# Borne_de_satisfaction_V0.net
KiCad netlist of a schematic drawn in EAGLE
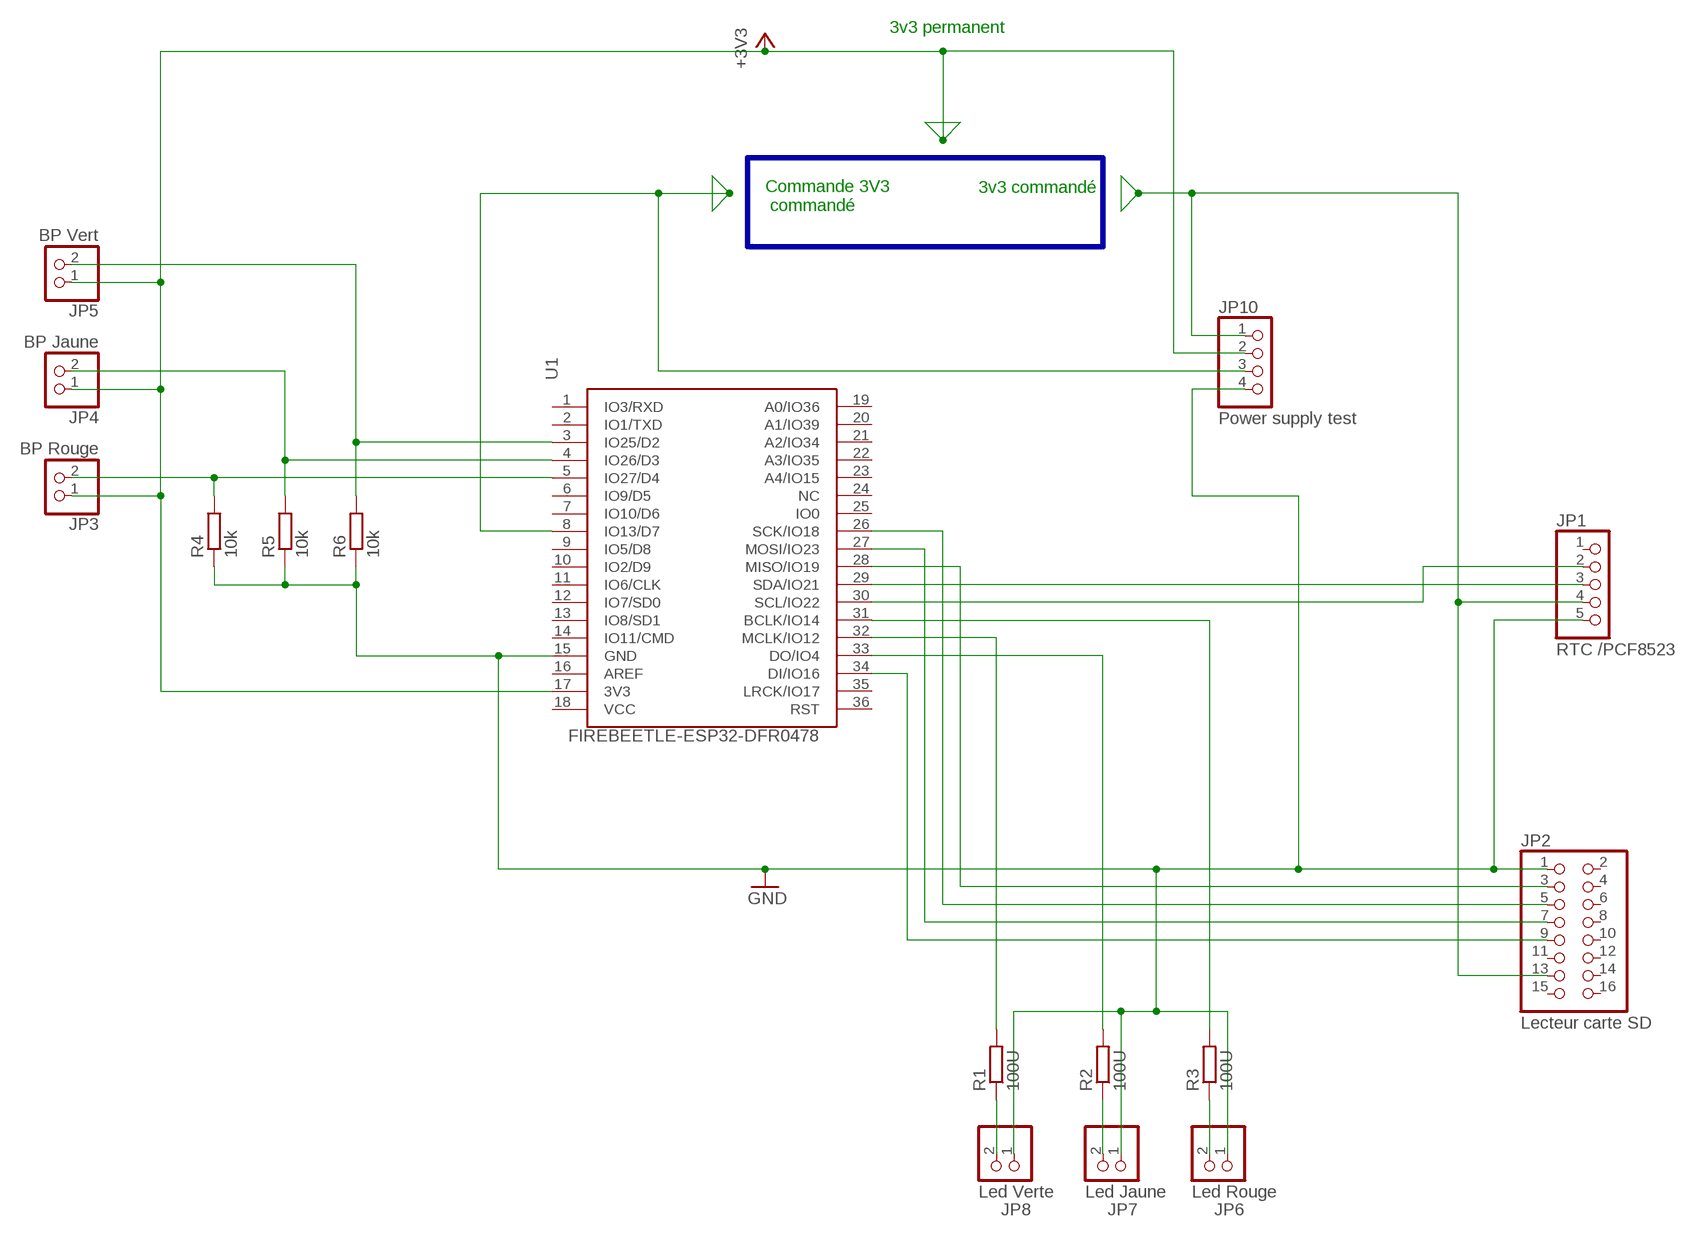
[diagram p0: schematic, sheet 1]

(export (version "E")
  (design (tool "Eeschema 10.0.6"))
  (components
    (comp (ref "JP1")
      (value "RTC /PCF8523")
      (footprint "eagle-import:1X05")
      (libsource (lib "eagle-import") (part "PINHD-1X5"))
    )
    (comp (ref "JP2")
      (value "Lecteur carte SD")
      (footprint "eagle-import:2X08")
      (libsource (lib "eagle-import") (part "PINHD-2X8"))
    )
    (comp (ref "JP3")
      (value "BP Rouge")
      (footprint "eagle-import:1X02")
      (libsource (lib "eagle-import") (part "PINHD-1X2"))
    )
    (comp (ref "JP4")
      (value "BP Jaune")
      (footprint "eagle-import:1X02")
      (libsource (lib "eagle-import") (part "PINHD-1X2"))
    )
    (comp (ref "JP5")
      (value "BP Vert")
      (footprint "eagle-import:1X02")
      (libsource (lib "eagle-import") (part "PINHD-1X2"))
    )
    (comp (ref "JP6")
      (value "Led Rouge")
      (footprint "eagle-import:1X02")
      (libsource (lib "eagle-import") (part "PINHD-1X2"))
    )
    (comp (ref "JP7")
      (value "Led Jaune")
      (footprint "eagle-import:1X02")
      (libsource (lib "eagle-import") (part "PINHD-1X2"))
    )
    (comp (ref "JP8")
      (value "Led Verte")
      (footprint "eagle-import:1X02")
      (libsource (lib "eagle-import") (part "PINHD-1X2"))
    )
    (comp (ref "JP10")
      (value "Power supply test")
      (footprint "eagle-import:1X04")
      (libsource (lib "eagle-import") (part "PINHD-1X4"))
    )
    (comp (ref "R1")
      (value "100U")
      (footprint "eagle-import:0207_10")
      (libsource (lib "eagle-import") (part "R-EU_0207/10"))
    )
    (comp (ref "R2")
      (value "100U")
      (footprint "eagle-import:0207_10")
      (libsource (lib "eagle-import") (part "R-EU_0207/10"))
    )
    (comp (ref "R3")
      (value "100U")
      (footprint "eagle-import:0207_10")
      (libsource (lib "eagle-import") (part "R-EU_0207/10"))
    )
    (comp (ref "R4")
      (value "10k")
      (footprint "eagle-import:0207_10")
      (libsource (lib "eagle-import") (part "R-EU_0207/10"))
    )
    (comp (ref "R5")
      (value "10k")
      (footprint "eagle-import:0207_10")
      (libsource (lib "eagle-import") (part "R-EU_0207/10"))
    )
    (comp (ref "R6")
      (value "10k")
      (footprint "eagle-import:0207_10")
      (libsource (lib "eagle-import") (part "R-EU_0207/10"))
    )
    (comp (ref "U1")
      (value "FIREBEETLE-ESP32-DFR0478")
      (footprint "eagle-import:FIREBEETLE_ESP32")
      (fields
        (field (name "MANUFACTURER_PART_NUMBER") "DFR0478")
        (field (name "MOUSER_PART_NUMBER") "426-DFR0478")
      )
      (libsource (lib "eagle-import") (part "FIREBEETLE-ESP32-DFR0478"))
    )
  )
  (nets
    (net (code "1") (name "+3V3") (class "Default")
      (node (ref "JP10") (pin "2") (pinfunction "2_2") (pintype "passive"))
      (node (ref "JP3") (pin "1") (pinfunction "1_1") (pintype "passive"))
      (node (ref "JP4") (pin "1") (pinfunction "1_1") (pintype "passive"))
      (node (ref "JP5") (pin "1") (pinfunction "1_1") (pintype "passive"))
      (node (ref "U1") (pin "17") (pinfunction "3V3_17") (pintype "bidirectional"))
    )
    (net (code "2") (name "GND") (class "Default")
      (node (ref "JP1") (pin "5") (pinfunction "5_5") (pintype "passive"))
      (node (ref "JP10") (pin "4") (pinfunction "4_4") (pintype "passive"))
      (node (ref "JP2") (pin "1") (pinfunction "1_1") (pintype "passive"))
      (node (ref "JP6") (pin "1") (pinfunction "1_1") (pintype "passive"))
      (node (ref "JP7") (pin "1") (pinfunction "1_1") (pintype "passive"))
      (node (ref "JP8") (pin "1") (pinfunction "1_1") (pintype "passive"))
      (node (ref "R4") (pin "1") (pinfunction "1_1") (pintype "passive"))
      (node (ref "R5") (pin "1") (pinfunction "1_1") (pintype "passive"))
      (node (ref "R6") (pin "1") (pinfunction "1_1") (pintype "passive"))
      (node (ref "U1") (pin "15") (pinfunction "GND_15") (pintype "bidirectional"))
    )
    (net (code "3") (name "Net-(JP1-Pad4)") (class "Default")
      (node (ref "JP1") (pin "4") (pinfunction "4_4") (pintype "passive"))
      (node (ref "JP10") (pin "1") (pinfunction "1_1") (pintype "passive"))
      (node (ref "JP2") (pin "13") (pinfunction "13_13") (pintype "passive"))
    )
    (net (code "4") (name "Net-(JP6-Pad2)") (class "Default")
      (node (ref "JP6") (pin "2") (pinfunction "2_2") (pintype "passive"))
      (node (ref "R3") (pin "1") (pinfunction "1_1") (pintype "passive"))
    )
    (net (code "5") (name "Net-(JP7-Pad2)") (class "Default")
      (node (ref "JP7") (pin "2") (pinfunction "2_2") (pintype "passive"))
      (node (ref "R2") (pin "1") (pinfunction "1_1") (pintype "passive"))
    )
    (net (code "6") (name "Net-(JP8-Pad2)") (class "Default")
      (node (ref "JP8") (pin "2") (pinfunction "2_2") (pintype "passive"))
      (node (ref "R1") (pin "1") (pinfunction "1_1") (pintype "passive"))
    )
    (net (code "7") (name "Net-(U1-BCLK{slash}IO14)") (class "Default")
      (node (ref "R3") (pin "2") (pinfunction "2_2") (pintype "passive"))
      (node (ref "U1") (pin "31") (pinfunction "BCLK/IO14_31") (pintype "bidirectional"))
    )
    (net (code "8") (name "Net-(U1-DI{slash}IO16)") (class "Default")
      (node (ref "JP2") (pin "9") (pinfunction "9_9") (pintype "passive"))
      (node (ref "U1") (pin "34") (pinfunction "DI/IO16_34") (pintype "bidirectional"))
    )
    (net (code "9") (name "Net-(U1-DO{slash}IO4)") (class "Default")
      (node (ref "R2") (pin "2") (pinfunction "2_2") (pintype "passive"))
      (node (ref "U1") (pin "33") (pinfunction "DO/IO4_33") (pintype "bidirectional"))
    )
    (net (code "10") (name "Net-(U1-IO13{slash}D7)") (class "Default")
      (node (ref "JP10") (pin "3") (pinfunction "3_3") (pintype "passive"))
      (node (ref "U1") (pin "8") (pinfunction "IO13/D7_8") (pintype "bidirectional"))
    )
    (net (code "11") (name "Net-(U1-IO25{slash}D2)") (class "Default")
      (node (ref "JP5") (pin "2") (pinfunction "2_2") (pintype "passive"))
      (node (ref "R6") (pin "2") (pinfunction "2_2") (pintype "passive"))
      (node (ref "U1") (pin "3") (pinfunction "IO25/D2_3") (pintype "bidirectional"))
    )
    (net (code "12") (name "Net-(U1-IO26{slash}D3)") (class "Default")
      (node (ref "JP4") (pin "2") (pinfunction "2_2") (pintype "passive"))
      (node (ref "R5") (pin "2") (pinfunction "2_2") (pintype "passive"))
      (node (ref "U1") (pin "4") (pinfunction "IO26/D3_4") (pintype "bidirectional"))
    )
    (net (code "13") (name "Net-(U1-IO27{slash}D4)") (class "Default")
      (node (ref "JP3") (pin "2") (pinfunction "2_2") (pintype "passive"))
      (node (ref "R4") (pin "2") (pinfunction "2_2") (pintype "passive"))
      (node (ref "U1") (pin "5") (pinfunction "IO27/D4_5") (pintype "bidirectional"))
    )
    (net (code "14") (name "Net-(U1-MCLK{slash}IO12)") (class "Default")
      (node (ref "R1") (pin "2") (pinfunction "2_2") (pintype "passive"))
      (node (ref "U1") (pin "32") (pinfunction "MCLK/IO12_32") (pintype "bidirectional"))
    )
    (net (code "15") (name "Net-(U1-MISO{slash}IO19)") (class "Default")
      (node (ref "JP2") (pin "3") (pinfunction "3_3") (pintype "passive"))
      (node (ref "U1") (pin "28") (pinfunction "MISO/IO19_28") (pintype "bidirectional"))
    )
    (net (code "16") (name "Net-(U1-MOSI{slash}IO23)") (class "Default")
      (node (ref "JP2") (pin "7") (pinfunction "7_7") (pintype "passive"))
      (node (ref "U1") (pin "27") (pinfunction "MOSI/IO23_27") (pintype "bidirectional"))
    )
    (net (code "17") (name "Net-(U1-SCK{slash}IO18)") (class "Default")
      (node (ref "JP2") (pin "5") (pinfunction "5_5") (pintype "passive"))
      (node (ref "U1") (pin "26") (pinfunction "SCK/IO18_26") (pintype "bidirectional"))
    )
    (net (code "18") (name "Net-(U1-SCL{slash}IO22)") (class "Default")
      (node (ref "JP1") (pin "2") (pinfunction "2_2") (pintype "passive"))
      (node (ref "U1") (pin "30") (pinfunction "SCL/IO22_30") (pintype "bidirectional"))
    )
    (net (code "19") (name "Net-(U1-SDA{slash}IO21)") (class "Default")
      (node (ref "JP1") (pin "3") (pinfunction "3_3") (pintype "passive"))
      (node (ref "U1") (pin "29") (pinfunction "SDA/IO21_29") (pintype "bidirectional"))
    )
    (net (code "20") (name "unconnected-(JP1-Pad1)") (class "Default")
      (node (ref "JP1") (pin "1") (pinfunction "1_1") (pintype "passive"))
    )
    (net (code "21") (name "unconnected-(JP2-Pad2)") (class "Default")
      (node (ref "JP2") (pin "2") (pinfunction "2_2") (pintype "passive"))
    )
    (net (code "22") (name "unconnected-(JP2-Pad4)") (class "Default")
      (node (ref "JP2") (pin "4") (pinfunction "4_4") (pintype "passive"))
    )
    (net (code "23") (name "unconnected-(JP2-Pad6)") (class "Default")
      (node (ref "JP2") (pin "6") (pinfunction "6_6") (pintype "passive"))
    )
    (net (code "24") (name "unconnected-(JP2-Pad8)") (class "Default")
      (node (ref "JP2") (pin "8") (pinfunction "8_8") (pintype "passive"))
    )
    (net (code "25") (name "unconnected-(JP2-Pad10)") (class "Default")
      (node (ref "JP2") (pin "10") (pinfunction "10_10") (pintype "passive"))
    )
    (net (code "26") (name "unconnected-(JP2-Pad11)") (class "Default")
      (node (ref "JP2") (pin "11") (pinfunction "11_11") (pintype "passive"))
    )
    (net (code "27") (name "unconnected-(JP2-Pad12)") (class "Default")
      (node (ref "JP2") (pin "12") (pinfunction "12_12") (pintype "passive"))
    )
    (net (code "28") (name "unconnected-(JP2-Pad14)") (class "Default")
      (node (ref "JP2") (pin "14") (pinfunction "14_14") (pintype "passive"))
    )
    (net (code "29") (name "unconnected-(JP2-Pad15)") (class "Default")
      (node (ref "JP2") (pin "15") (pinfunction "15_15") (pintype "passive"))
    )
    (net (code "30") (name "unconnected-(JP2-Pad16)") (class "Default")
      (node (ref "JP2") (pin "16") (pinfunction "16_16") (pintype "passive"))
    )
    (net (code "31") (name "unconnected-(U1-A0{slash}IO36-Pad19)") (class "Default")
      (node (ref "U1") (pin "19") (pinfunction "A0/IO36_19") (pintype "bidirectional"))
    )
    (net (code "32") (name "unconnected-(U1-A1{slash}IO39-Pad20)") (class "Default")
      (node (ref "U1") (pin "20") (pinfunction "A1/IO39_20") (pintype "bidirectional"))
    )
    (net (code "33") (name "unconnected-(U1-A2{slash}IO34-Pad21)") (class "Default")
      (node (ref "U1") (pin "21") (pinfunction "A2/IO34_21") (pintype "bidirectional"))
    )
    (net (code "34") (name "unconnected-(U1-A3{slash}IO35-Pad22)") (class "Default")
      (node (ref "U1") (pin "22") (pinfunction "A3/IO35_22") (pintype "bidirectional"))
    )
    (net (code "35") (name "unconnected-(U1-A4{slash}IO15-Pad23)") (class "Default")
      (node (ref "U1") (pin "23") (pinfunction "A4/IO15_23") (pintype "bidirectional"))
    )
    (net (code "36") (name "unconnected-(U1-AREF-Pad16)") (class "Default")
      (node (ref "U1") (pin "16") (pinfunction "AREF_16") (pintype "bidirectional"))
    )
    (net (code "37") (name "unconnected-(U1-IO0-Pad25)") (class "Default")
      (node (ref "U1") (pin "25") (pinfunction "IO0_25") (pintype "bidirectional"))
    )
    (net (code "38") (name "unconnected-(U1-IO1{slash}TXD-Pad2)") (class "Default")
      (node (ref "U1") (pin "2") (pinfunction "IO1/TXD_2") (pintype "bidirectional"))
    )
    (net (code "39") (name "unconnected-(U1-IO2{slash}D9-Pad10)") (class "Default")
      (node (ref "U1") (pin "10") (pinfunction "IO2/D9_10") (pintype "bidirectional"))
    )
    (net (code "40") (name "unconnected-(U1-IO3{slash}RXD-Pad1)") (class "Default")
      (node (ref "U1") (pin "1") (pinfunction "IO3/RXD_1") (pintype "bidirectional"))
    )
    (net (code "41") (name "unconnected-(U1-IO5{slash}D8-Pad9)") (class "Default")
      (node (ref "U1") (pin "9") (pinfunction "IO5/D8_9") (pintype "bidirectional"))
    )
    (net (code "42") (name "unconnected-(U1-IO6{slash}CLK-Pad11)") (class "Default")
      (node (ref "U1") (pin "11") (pinfunction "IO6/CLK_11") (pintype "bidirectional"))
    )
    (net (code "43") (name "unconnected-(U1-IO7{slash}SD0-Pad12)") (class "Default")
      (node (ref "U1") (pin "12") (pinfunction "IO7/SD0_12") (pintype "bidirectional"))
    )
    (net (code "44") (name "unconnected-(U1-IO8{slash}SD1-Pad13)") (class "Default")
      (node (ref "U1") (pin "13") (pinfunction "IO8/SD1_13") (pintype "bidirectional"))
    )
    (net (code "45") (name "unconnected-(U1-IO9{slash}D5-Pad6)") (class "Default")
      (node (ref "U1") (pin "6") (pinfunction "IO9/D5_6") (pintype "bidirectional"))
    )
    (net (code "46") (name "unconnected-(U1-IO10{slash}D6-Pad7)") (class "Default")
      (node (ref "U1") (pin "7") (pinfunction "IO10/D6_7") (pintype "bidirectional"))
    )
    (net (code "47") (name "unconnected-(U1-IO11{slash}CMD-Pad14)") (class "Default")
      (node (ref "U1") (pin "14") (pinfunction "IO11/CMD_14") (pintype "bidirectional"))
    )
    (net (code "48") (name "unconnected-(U1-LRCK{slash}IO17-Pad35)") (class "Default")
      (node (ref "U1") (pin "35") (pinfunction "LRCK/IO17_35") (pintype "bidirectional"))
    )
    (net (code "49") (name "unconnected-(U1-NC-Pad24)") (class "Default")
      (node (ref "U1") (pin "24") (pinfunction "NC_24") (pintype "no_connect"))
    )
    (net (code "50") (name "unconnected-(U1-RST-Pad36)") (class "Default")
      (node (ref "U1") (pin "36") (pinfunction "RST_36") (pintype "bidirectional"))
    )
    (net (code "51") (name "unconnected-(U1-VCC-Pad18)") (class "Default")
      (node (ref "U1") (pin "18") (pinfunction "VCC_18") (pintype "bidirectional"))
    )
  )
)
